# LowVoltageShutdownV2.net
KiCad netlist of a schematic drawn in EAGLE
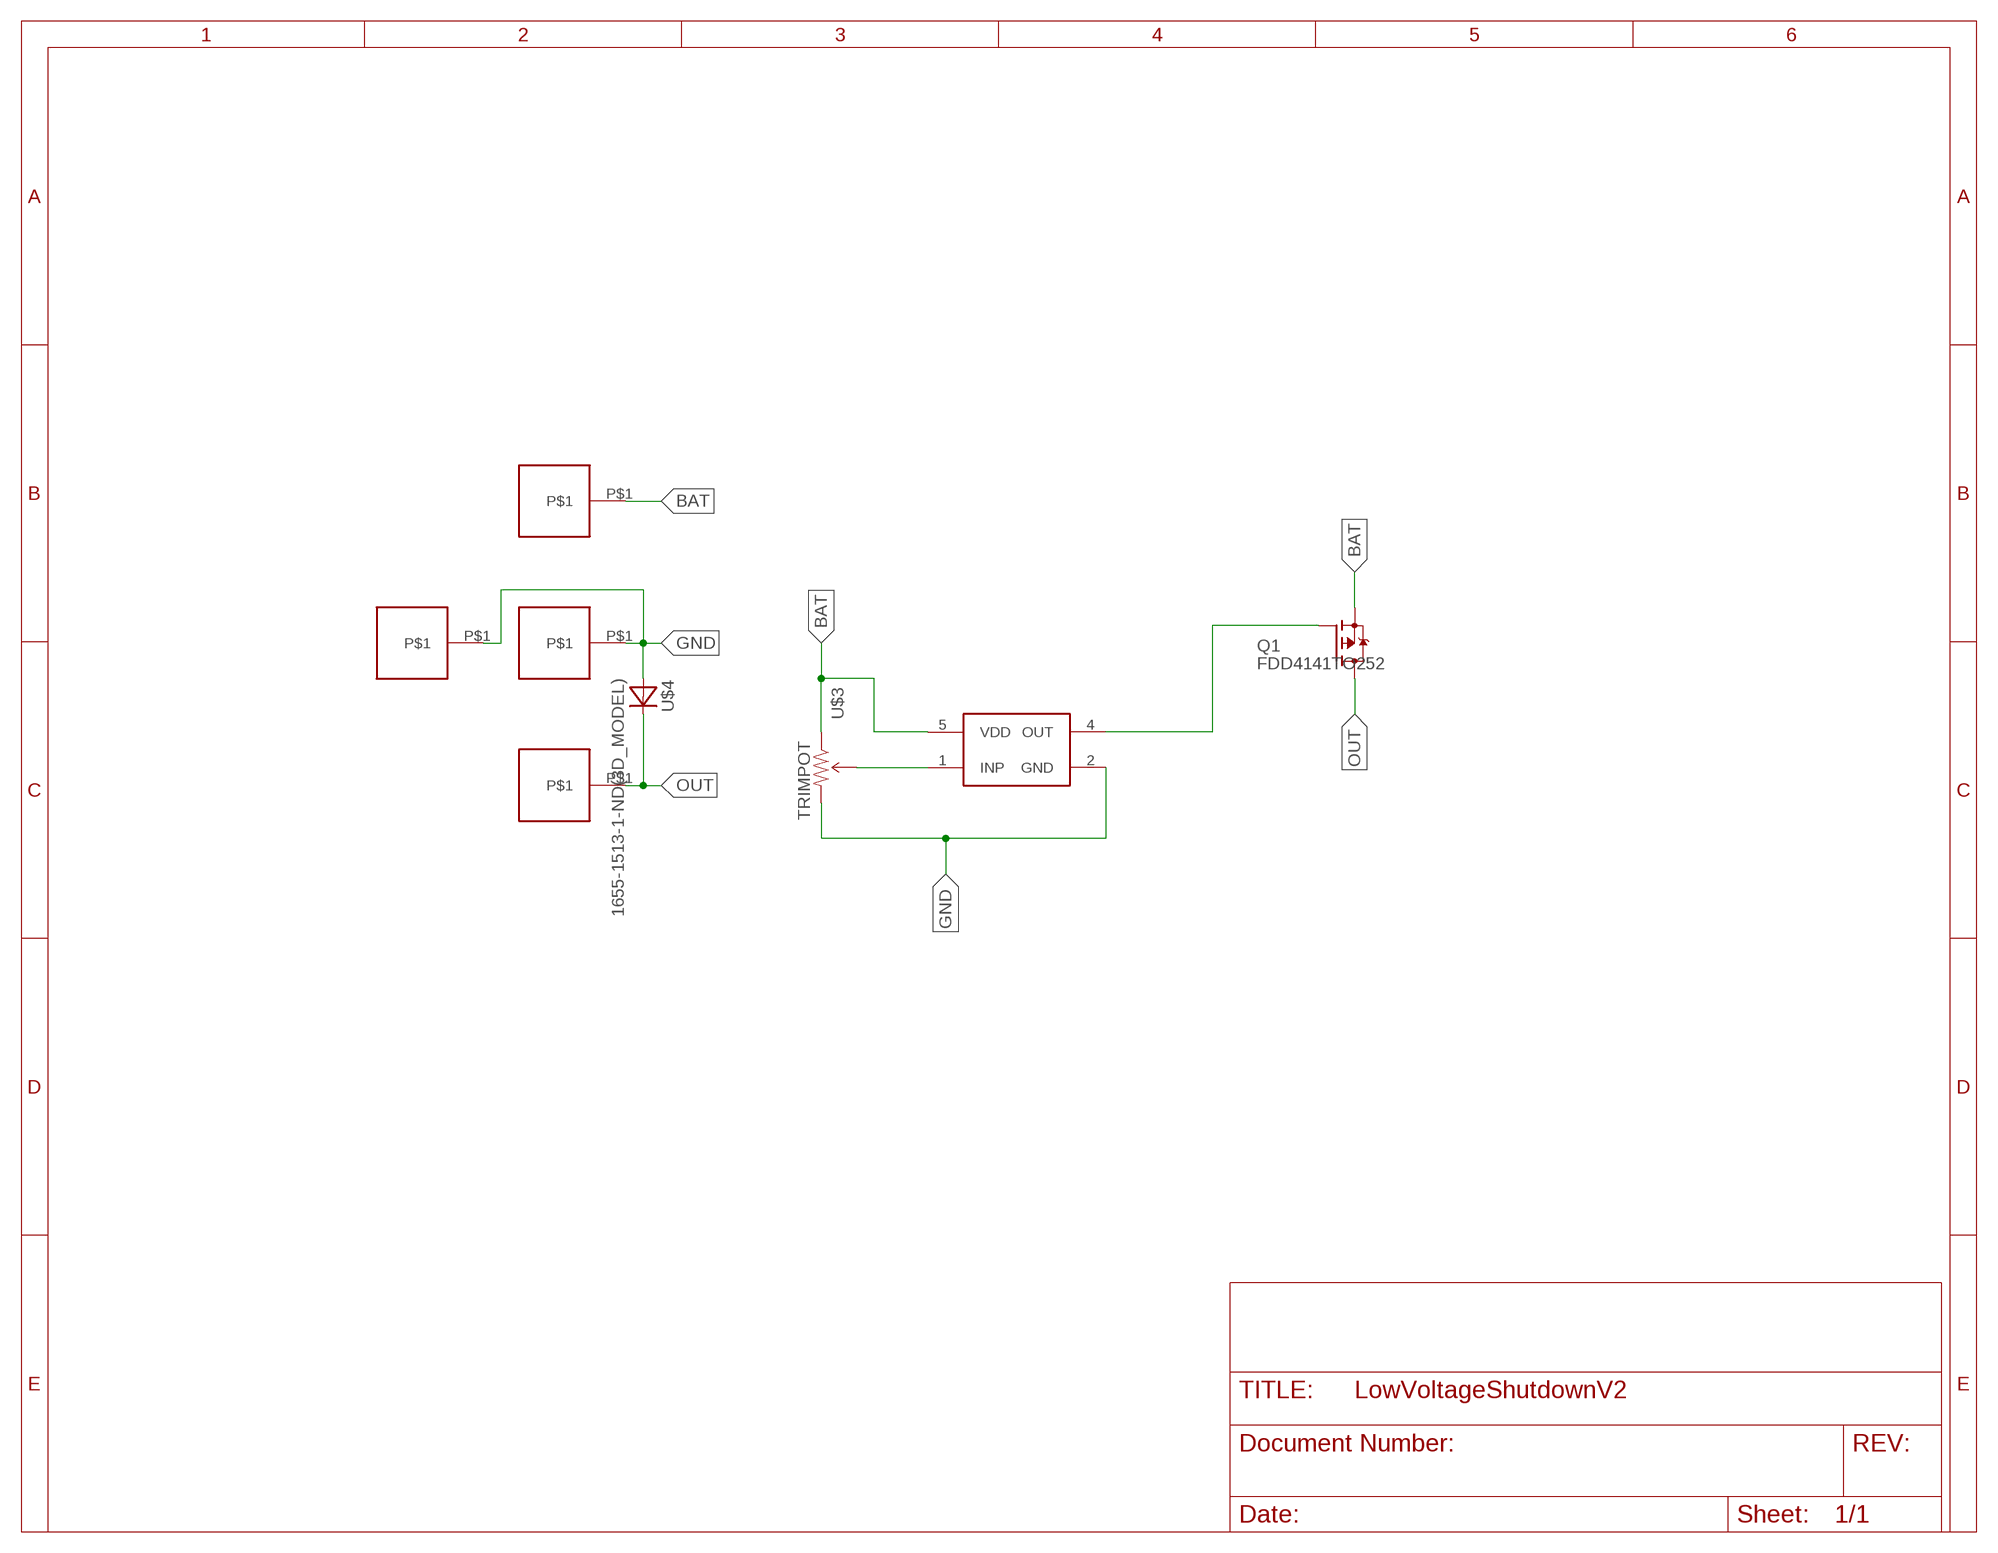
[diagram p0: schematic, sheet 1]

(export (version "E")
  (design (tool "Eeschema 10.0.6"))
  (components
    (comp (ref "OUT")
      (value "16G")
      (footprint "eagle-import:16G")
      (libsource (lib "eagle-import") (part "16G"))
    )
    (comp (ref "OUT1")
      (value "16G")
      (footprint "eagle-import:16G")
      (libsource (lib "eagle-import") (part "16G"))
    )
    (comp (ref "Q1")
      (value "FDD4141TO252")
      (footprint "eagle-import:TO252")
      (libsource (lib "eagle-import") (part "FDD4141TO252"))
    )
    (comp (ref "U$1")
      (value "MIC842L(3D_MODEL)")
      (footprint "eagle-import:SOTFL65P210X110-5")
      (libsource (lib "eagle-import") (part "MIC842L(3D_MODEL)"))
    )
    (comp (ref "U$3")
      (value "TRIMPOT")
      (footprint "eagle-import:490-2877-ND")
      (libsource (lib "eagle-import") (part "TRIMPOT"))
    )
    (comp (ref "U$4")
      (value "1655-1513-1-ND(3D_MODEL)")
      (footprint "eagle-import:DIOAD1950W130L900D530B")
      (libsource (lib "eagle-import") (part "1655-1513-1-ND(3D_MODEL)"))
    )
    (comp (ref "U$5")
      (value "450PAD")
      (footprint "eagle-import:450PAD")
      (libsource (lib "eagle-import") (part "450PAD"))
    )
    (comp (ref "U$6")
      (value "450PAD")
      (footprint "eagle-import:450PAD")
      (libsource (lib "eagle-import") (part "450PAD"))
    )
  )
  (nets
    (net (code "1") (name "BAT") (class "Default")
      (node (ref "Q1") (pin "2") (pinfunction "S_2") (pintype "passive"))
      (node (ref "U$1") (pin "5") (pinfunction "VDD_5") (pintype "bidirectional"))
      (node (ref "U$3") (pin "P$1") (pinfunction "CCW_P$1") (pintype "passive"))
      (node (ref "U$5") (pin "P$1") (pinfunction "P$1_P$1") (pintype "bidirectional"))
    )
    (net (code "2") (name "GND") (class "Default")
      (node (ref "OUT1") (pin "P$1") (pinfunction "P$1_P$1") (pintype "bidirectional"))
      (node (ref "U$1") (pin "2") (pinfunction "GND_2") (pintype "bidirectional"))
      (node (ref "U$3") (pin "P$3") (pinfunction "CW_P$3") (pintype "passive"))
      (node (ref "U$4") (pin "2") (pinfunction "A_2") (pintype "passive"))
      (node (ref "U$6") (pin "P$1") (pinfunction "P$1_P$1") (pintype "bidirectional"))
    )
    (net (code "3") (name "Net-(Q1-G)") (class "Default")
      (node (ref "Q1") (pin "1") (pinfunction "G_1") (pintype "passive"))
      (node (ref "U$1") (pin "4") (pinfunction "OUT_4") (pintype "bidirectional"))
    )
    (net (code "4") (name "Net-(U$1-INP)") (class "Default")
      (node (ref "U$1") (pin "1") (pinfunction "INP_1") (pintype "bidirectional"))
      (node (ref "U$3") (pin "P$2") (pinfunction "WIPER_P$2") (pintype "passive"))
    )
    (net (code "5") (name "OUT") (class "Default")
      (node (ref "OUT") (pin "P$1") (pinfunction "P$1_P$1") (pintype "bidirectional"))
      (node (ref "Q1") (pin "3") (pinfunction "D_3") (pintype "passive"))
      (node (ref "U$4") (pin "1") (pinfunction "C_1") (pintype "passive"))
    )
  )
)
